# gyro.net
KiCad netlist of a schematic drawn in EAGLE
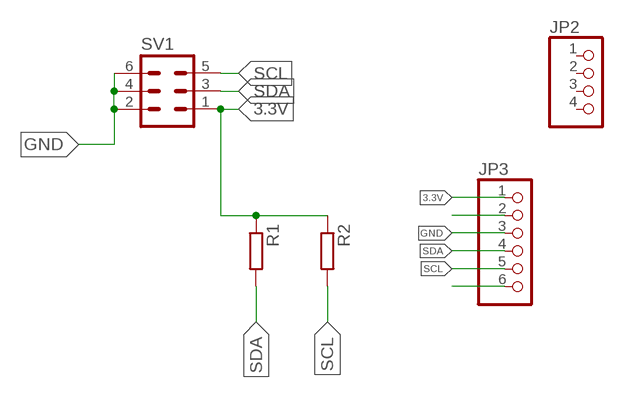
[diagram p0: schematic, sheet 1]

(export (version "E")
  (design (tool "Eeschema 10.0.6"))
  (components
    (comp (ref "JP2")
      (value "PINHD-1X4")
      (footprint "eagle-import:1X04")
      (libsource (lib "eagle-import") (part "PINHD-1X4"))
    )
    (comp (ref "JP3")
      (value "PINHD-1X6")
      (footprint "eagle-import:1X06")
      (libsource (lib "eagle-import") (part "PINHD-1X6"))
    )
    (comp (ref "R1")
      (value "R-EU_0309/12")
      (footprint "eagle-import:0309_12")
      (libsource (lib "eagle-import") (part "R-EU_0309/12"))
    )
    (comp (ref "R2")
      (value "R-EU_0309/12")
      (footprint "eagle-import:0309_12")
      (libsource (lib "eagle-import") (part "R-EU_0309/12"))
    )
    (comp (ref "SV1")
      (value "ML6")
      (footprint "eagle-import:ML6")
      (libsource (lib "eagle-import") (part "ML6"))
    )
  )
  (nets
    (net (code "1") (name "3.3V") (class "Default")
      (node (ref "JP3") (pin "1") (pinfunction "1_1") (pintype "passive"))
      (node (ref "R1") (pin "1") (pinfunction "1_1") (pintype "passive"))
      (node (ref "R2") (pin "1") (pinfunction "1_1") (pintype "passive"))
      (node (ref "SV1") (pin "1") (pinfunction "1_1") (pintype "passive"))
    )
    (net (code "2") (name "GND") (class "Default")
      (node (ref "JP3") (pin "3") (pinfunction "3_3") (pintype "passive"))
      (node (ref "SV1") (pin "2") (pinfunction "2_2") (pintype "passive"))
      (node (ref "SV1") (pin "4") (pinfunction "4_4") (pintype "passive"))
      (node (ref "SV1") (pin "6") (pinfunction "6_6") (pintype "passive"))
    )
    (net (code "3") (name "SCL") (class "Default")
      (node (ref "JP3") (pin "5") (pinfunction "5_5") (pintype "passive"))
      (node (ref "R2") (pin "2") (pinfunction "2_2") (pintype "passive"))
      (node (ref "SV1") (pin "5") (pinfunction "5_5") (pintype "passive"))
    )
    (net (code "4") (name "SDA") (class "Default")
      (node (ref "JP3") (pin "4") (pinfunction "4_4") (pintype "passive"))
      (node (ref "R1") (pin "2") (pinfunction "2_2") (pintype "passive"))
      (node (ref "SV1") (pin "3") (pinfunction "3_3") (pintype "passive"))
    )
    (net (code "5") (name "unconnected-(JP2-Pad1)") (class "Default")
      (node (ref "JP2") (pin "1") (pinfunction "1_1") (pintype "passive"))
    )
    (net (code "6") (name "unconnected-(JP2-Pad2)") (class "Default")
      (node (ref "JP2") (pin "2") (pinfunction "2_2") (pintype "passive"))
    )
    (net (code "7") (name "unconnected-(JP2-Pad3)") (class "Default")
      (node (ref "JP2") (pin "3") (pinfunction "3_3") (pintype "passive"))
    )
    (net (code "8") (name "unconnected-(JP2-Pad4)") (class "Default")
      (node (ref "JP2") (pin "4") (pinfunction "4_4") (pintype "passive"))
    )
    (net (code "9") (name "unconnected-(JP3-Pad2)") (class "Default")
      (node (ref "JP3") (pin "2") (pinfunction "2_2") (pintype "passive"))
    )
    (net (code "10") (name "unconnected-(JP3-Pad6)") (class "Default")
      (node (ref "JP3") (pin "6") (pinfunction "6_6") (pintype "passive"))
    )
  )
)
